# LinearRegulator.net
KiCad netlist of a schematic drawn in Altium Designer
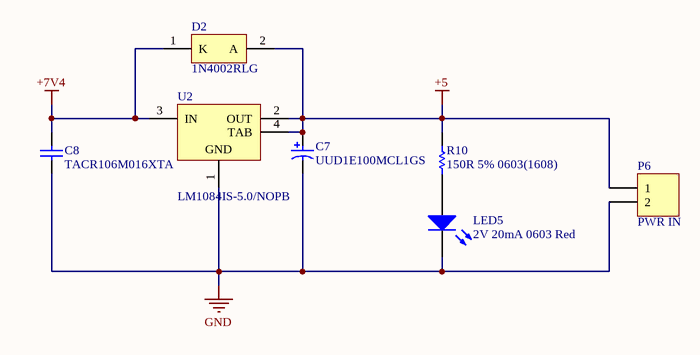
[diagram p0: LinearRegulator.SchDoc]

(export (version "E")
  (design (tool "Eeschema 10.0.6"))
  (components
    (comp (ref "C7")
      (value "UUD1E100MCL1GS")
      (footprint "NIC-CAPA2-4X5.8_V")
      (fields (field (name "MANUFACTURER") "Nichicon"))
      (libsource (lib "Altium Content Vault") (part "NIC-CAP-P-2"))
    )
    (comp (ref "C8")
      (value "TACR106M016XTA")
      (footprint "CAPC2014X150X70NL20")
      (fields (field (name "MANUFACTURER") "AVX Interconnect / Elco"))
      (libsource (lib "Altium Content Vault") (part "CAP"))
    )
    (comp (ref "D2")
      (value "1N4002RLG")
      (footprint "ONSC-AXIAL_LEAD-2-59-10_P")
      (description "Standard Recovery Rectifier, 2-Pin Axial_Lead, Pb-Free, Tape and Reel")
      (fields (field (name "MANUFACTURER") "On Semiconductor"))
      (libsource (lib "Altium Content Vault") (part "ONSC-D-K1A2-2_A"))
    )
    (comp (ref "LED5")
      (value "2V 20mA 0603 Red")
      (footprint "0603_A")
      (description "SMD mono-color Chip LED, WL-SMCW, Red")
      (fields (field (name "MANUFACTURER") "Wuerth Elektronik") (field (name "PARTNUMBER") "150060RS75000"))
      (libsource (lib "Altium Content Vault") (part "WE-LED_K1A2-2"))
    )
    (comp (ref "P6")
      (value "PWR IN")
      (footprint "HDR1X2")
      (description "Header, 2-Pin")
      (fields (field (name "PUBLISHER") "Altium Limited"))
      (libsource (lib "Miscellaneous Connectors") (part "Header 2"))
    )
    (comp (ref "R10")
      (value "150R 5% 0603(1608)")
      (footprint "RESC0603(1608)_L")
      (description "150R 0.1W 5% 0603 (1608 Metric)  SMD")
      (fields (field (name "POWER") "0.1 W") (field (name "TOLERANCE") "5 %"))
      (libsource (lib "Altium Content Vault") (part "RES"))
    )
    (comp (ref "U2")
      (value "LM1084IS-5.0/NOPB")
      (footprint "KTT0003B_L")
      (description "5A Low Dropout Positive Regulators, 3-pin TO-263, Pb-Free")
      (fields (field (name "MANUFACTURER") "Texas Instruments"))
      (libsource (lib "Altium Content Vault") (part "PM-REG-LM1086-SOT4"))
    )
  )
  (nets
    (net (code "1") (name "+5") (class "Default")
      (node (ref "C7") (pin "1") (pinfunction "1_1") (pintype "passive"))
      (node (ref "D2") (pin "2") (pinfunction "A_2") (pintype "passive"))
      (node (ref "P6") (pin "1") (pinfunction "1_1") (pintype "passive"))
      (node (ref "R10") (pin "2") (pinfunction "2_2") (pintype "passive"))
      (node (ref "U2") (pin "2") (pinfunction "OUT_2") (pintype "power_in"))
      (node (ref "U2") (pin "4") (pinfunction "TAB_4") (pintype "power_in"))
    )
    (net (code "2") (name "+7V4") (class "Default")
      (node (ref "C8") (pin "2") (pinfunction "2_2") (pintype "passive"))
      (node (ref "D2") (pin "1") (pinfunction "K_1") (pintype "passive"))
      (node (ref "U2") (pin "3") (pinfunction "IN_3") (pintype "power_in"))
    )
    (net (code "3") (name "GND") (class "Default")
      (node (ref "C7") (pin "2") (pinfunction "2_2") (pintype "passive"))
      (node (ref "C8") (pin "1") (pinfunction "1_1") (pintype "passive"))
      (node (ref "LED5") (pin "1") (pinfunction "K_1") (pintype "passive"))
      (node (ref "P6") (pin "2") (pinfunction "2_2") (pintype "passive"))
      (node (ref "U2") (pin "1") (pinfunction "GND_1") (pintype "power_in"))
    )
    (net (code "4") (name "Net-(LED5-A)") (class "Default")
      (node (ref "LED5") (pin "2") (pinfunction "A_2") (pintype "passive"))
      (node (ref "R10") (pin "1") (pinfunction "1_1") (pintype "passive"))
    )
  )
)
